# 8086_ELEVATOR_PROJECT.net
KiCad netlist of a schematic drawn in EasyEDA
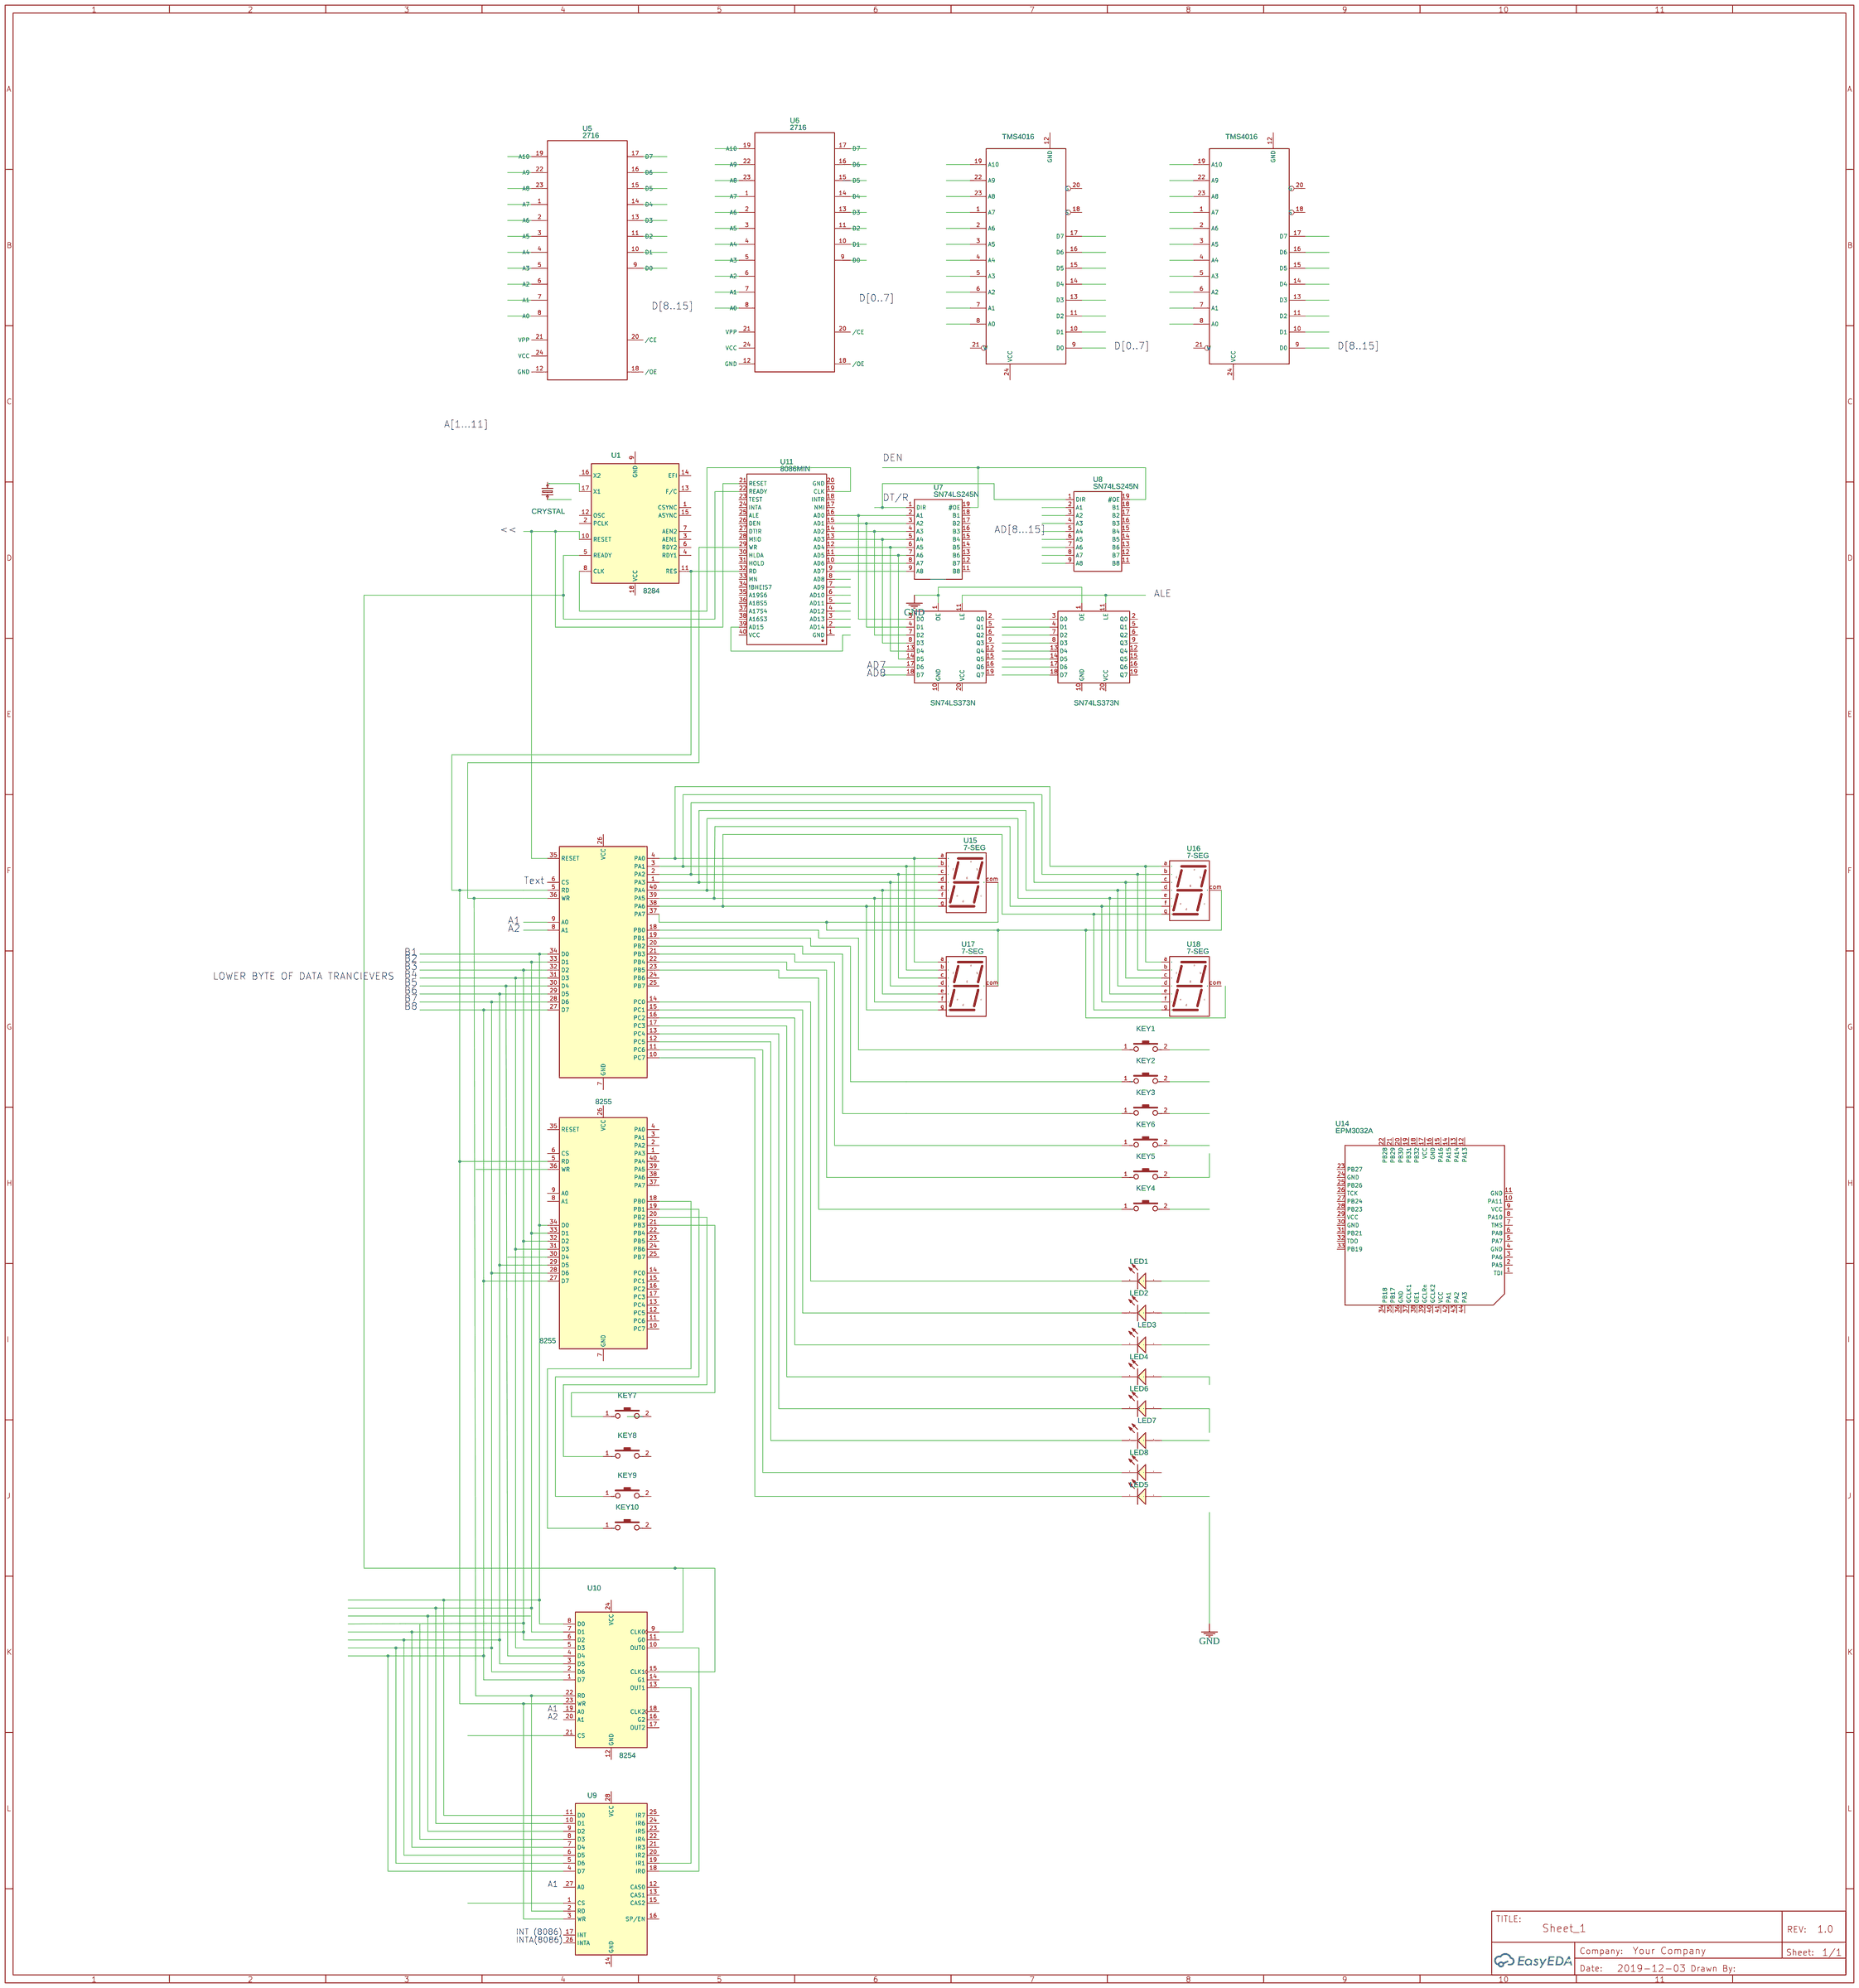
[diagram p0: schematic sheet]

(export (version "E")
  (design (tool "Eeschema 10.0.6"))
  (components
    (comp (ref "KEY1")
      (value "6*6*5 Silicone silent key button")
      (fields (field (name "BOM_Supplier Part") "C61120"))
      (libsource (lib "") (part "Unknown_1300_1140"))
    )
    (comp (ref "KEY2")
      (value "6*6*5 Silicone silent key button")
      (fields (field (name "BOM_Supplier Part") "C61120"))
      (libsource (lib "") (part "Unknown_1300_1180"))
    )
    (comp (ref "KEY3")
      (value "6*6*5 Silicone silent key button")
      (fields (field (name "BOM_Supplier Part") "C61120"))
      (libsource (lib "") (part "Unknown_1300_1220"))
    )
    (comp (ref "KEY4")
      (value "6*6*5 Silicone silent key button")
      (fields (field (name "BOM_Supplier Part") "C61120"))
      (libsource (lib "") (part "Unknown_1300_1340"))
    )
    (comp (ref "KEY5")
      (value "6*6*5 Silicone silent key button")
      (fields (field (name "BOM_Supplier Part") "C61120"))
      (libsource (lib "") (part "Unknown_1300_1300"))
    )
    (comp (ref "KEY6")
      (value "6*6*5 Silicone silent key button")
      (fields (field (name "BOM_Supplier Part") "C61120"))
      (libsource (lib "") (part "Unknown_1300_1260"))
    )
    (comp (ref "KEY7")
      (value "6*6*5 Silicone silent key button")
      (fields (field (name "BOM_Supplier Part") "C61120"))
      (libsource (lib "") (part "Unknown_650_1600"))
    )
    (comp (ref "KEY8")
      (value "6*6*5 Silicone silent key button")
      (fields (field (name "BOM_Supplier Part") "C61120"))
      (libsource (lib "") (part "Unknown_650_1650"))
    )
    (comp (ref "KEY9")
      (value "6*6*5 Silicone silent key button")
      (fields (field (name "BOM_Supplier Part") "C61120"))
      (libsource (lib "") (part "Unknown_650_1700"))
    )
    (comp (ref "KEY10")
      (value "6*6*5 Silicone silent key button")
      (fields (field (name "BOM_Supplier Part") "C61120"))
      (libsource (lib "") (part "Unknown_650_1740"))
    )
    (comp (ref "LED1")
      (value "LEDBlue light")
      (fields (field (name "BOM_Supplier Part") "C69273"))
      (libsource (lib "") (part "Unknown_1300_1430"))
    )
    (comp (ref "LED2")
      (value "LEDBlue light")
      (fields (field (name "BOM_Supplier Part") "C69273"))
      (libsource (lib "") (part "Unknown_1300_1470"))
    )
    (comp (ref "LED3")
      (value "LEDBlue light")
      (fields (field (name "BOM_Supplier Part") "C69273"))
      (libsource (lib "") (part "Unknown_1300_1510"))
    )
    (comp (ref "LED4")
      (value "LEDBlue light")
      (fields (field (name "BOM_Supplier Part") "C69273"))
      (libsource (lib "") (part "Unknown_1300_1550"))
    )
    (comp (ref "LED5")
      (value "LEDBlue light")
      (fields (field (name "BOM_Supplier Part") "C69273"))
      (libsource (lib "") (part "Unknown_1300_1700"))
    )
    (comp (ref "LED6")
      (value "LEDBlue light")
      (fields (field (name "BOM_Supplier Part") "C69273"))
      (libsource (lib "") (part "Unknown_1300_1590"))
    )
    (comp (ref "LED7")
      (value "LEDBlue light")
      (fields (field (name "BOM_Supplier Part") "C69273"))
      (libsource (lib "") (part "Unknown_1300_1630"))
    )
    (comp (ref "LED8")
      (value "LEDBlue light")
      (fields (field (name "BOM_Supplier Part") "C69273"))
      (libsource (lib "") (part "Unknown_1300_1670"))
    )
    (comp (ref "Q1") (value "CRYSTAL") (libsource (lib "") (part "Unknown_550_440")))
    (comp (ref "U1") (value "8284") (libsource (lib "") (part "Unknown_660_480")))
    (comp (ref "U2") (value "TMS4016") (libsource (lib "") (part "Unknown_1150_140")))
    (comp (ref "U3") (value "TMS4016") (libsource (lib "") (part "Unknown_1430_140")))
    (comp (ref "U4") (value "8255") (libsource (lib "") (part "Unknown_620_1030")))
    (comp (ref "U5")
      (value "2716")
      (fields (field (name "BOM_Manufacturer Part") "27C16"))
      (libsource (lib "") (part "Unknown_550_130"))
    )
    (comp (ref "U6")
      (value "2716")
      (fields (field (name "BOM_Manufacturer Part") "27C16"))
      (libsource (lib "") (part "Unknown_810_120"))
    )
    (comp (ref "U7")
      (value "SN74LS245N")
      (fields (field (name "BOM_Supplier Part") "C352966"))
      (libsource (lib "") (part "Unknown_1040_510"))
    )
    (comp (ref "U8")
      (value "SN74LS245N")
      (fields (field (name "BOM_Supplier Part") "C352966"))
      (libsource (lib "") (part "Unknown_1240_500"))
    )
    (comp (ref "U9") (value "8259") (libsource (lib "") (part "Unknown_630_2180")))
    (comp (ref "U10") (value "8254") (libsource (lib "") (part "Unknown_630_1930")))
    (comp (ref "U11") (value "8086MIN") (libsource (lib "") (part "Unknown_850_520")))
    (comp (ref "U12")
      (value "SN74LS373N")
      (fields (field (name "BOM_Supplier Part") "C10423"))
      (libsource (lib "") (part "Unknown_1190_600"))
    )
    (comp (ref "U13")
      (value "SN74LS373N")
      (fields (field (name "BOM_Supplier Part") "C10423"))
      (libsource (lib "") (part "Unknown_1010_600"))
    )
    (comp (ref "U14") (value "EPM3032A") (libsource (lib "") (part "Unknown_1650_1360")))
    (comp (ref "U15") (value "7-SEG") (libsource (lib "") (part "Unknown_1080_930")))
    (comp (ref "U16") (value "7-SEG") (libsource (lib "") (part "Unknown_1360_940")))
    (comp (ref "U17") (value "7-SEG") (libsource (lib "") (part "Unknown_1080_1060")))
    (comp (ref "U18") (value "7-SEG") (libsource (lib "") (part "Unknown_1360_1060")))
    (comp (ref "U19") (value "8255") (libsource (lib "") (part "Unknown_620_1370")))
  )
  (nets
    (net (code "1") (name "GND") (class "Default")
      (node (ref "U12") (pin "1") (pinfunction "OE_1") (pintype "unspecified"))
      (node (ref "U13") (pin "1") (pinfunction "OE_1") (pintype "unspecified"))
    )
    (net (code "2") (name "Net-(U1-CLK)") (class "Default")
      (node (ref "U1") (pin "8") (pinfunction "CLK_8") (pintype "output"))
      (node (ref "U11") (pin "19") (pinfunction "CLK_19") (pintype "unspecified"))
    )
    (net (code "3") (name "Net-(U1-READY)") (class "Default")
      (node (ref "U1") (pin "5") (pinfunction "READY_5") (pintype "output"))
      (node (ref "U10") (pin "15") (pinfunction "CLK1_15") (pintype "input"))
      (node (ref "U10") (pin "9") (pinfunction "CLK0_9") (pintype "input"))
      (node (ref "U11") (pin "22") (pinfunction "READY_22") (pintype "unspecified"))
    )
    (net (code "4") (name "Net-(U1-RES)") (class "Default")
      (node (ref "U1") (pin "11") (pinfunction "RES_11") (pintype "input"))
      (node (ref "U10") (pin "23") (pinfunction "WR_23") (pintype "input"))
      (node (ref "U11") (pin "32") (pinfunction "RD_32") (pintype "unspecified"))
      (node (ref "U19") (pin "5") (pinfunction "RD_5") (pintype "input"))
      (node (ref "U4") (pin "5") (pinfunction "RD_5") (pintype "input"))
      (node (ref "U9") (pin "3") (pinfunction "WR_3") (pintype "input"))
    )
    (net (code "5") (name "Net-(U1-RESET)") (class "Default")
      (node (ref "U1") (pin "10") (pinfunction "RESET_10") (pintype "output"))
      (node (ref "U11") (pin "21") (pinfunction "RESET_21") (pintype "unspecified"))
      (node (ref "U4") (pin "35") (pinfunction "RESET_35") (pintype "input"))
    )
    (net (code "6") (name "Net-(U1-X1)") (class "Default")
      (node (ref "Q1") (pin "1") (pinfunction "1_1") (pintype "unspecified"))
      (node (ref "U1") (pin "17") (pinfunction "X1_17") (pintype "input"))
    )
    (net (code "7") (name "Net-(U4-PA0)") (class "Default")
      (node (ref "U15") (pin "a") (pinfunction "a_a") (pintype "input"))
      (node (ref "U16") (pin "a") (pinfunction "a_a") (pintype "input"))
      (node (ref "U17") (pin "a") (pinfunction "a_a") (pintype "input"))
      (node (ref "U18") (pin "a") (pinfunction "a_a") (pintype "input"))
      (node (ref "U4") (pin "4") (pinfunction "PA0_4") (pintype "bidirectional"))
    )
    (net (code "8") (name "Net-(U4-PA1)") (class "Default")
      (node (ref "U15") (pin "b") (pinfunction "b_b") (pintype "input"))
      (node (ref "U16") (pin "b") (pinfunction "b_b") (pintype "input"))
      (node (ref "U17") (pin "b") (pinfunction "b_b") (pintype "input"))
      (node (ref "U18") (pin "b") (pinfunction "b_b") (pintype "input"))
      (node (ref "U4") (pin "3") (pinfunction "PA1_3") (pintype "bidirectional"))
    )
    (net (code "9") (name "Net-(U4-PA2)") (class "Default")
      (node (ref "U15") (pin "c") (pinfunction "c_c") (pintype "input"))
      (node (ref "U16") (pin "c") (pinfunction "c_c") (pintype "input"))
      (node (ref "U17") (pin "c") (pinfunction "c_c") (pintype "input"))
      (node (ref "U18") (pin "c") (pinfunction "c_c") (pintype "input"))
      (node (ref "U4") (pin "2") (pinfunction "PA2_2") (pintype "bidirectional"))
    )
    (net (code "10") (name "Net-(U4-PA3)") (class "Default")
      (node (ref "U15") (pin "d") (pinfunction "d_d") (pintype "input"))
      (node (ref "U16") (pin "d") (pinfunction "d_d") (pintype "input"))
      (node (ref "U17") (pin "d") (pinfunction "d_d") (pintype "input"))
      (node (ref "U18") (pin "d") (pinfunction "d_d") (pintype "input"))
      (node (ref "U4") (pin "1") (pinfunction "PA3_1") (pintype "bidirectional"))
    )
    (net (code "11") (name "Net-(U4-PA4)") (class "Default")
      (node (ref "U15") (pin "e") (pinfunction "e_e") (pintype "input"))
      (node (ref "U16") (pin "e") (pinfunction "e_e") (pintype "input"))
      (node (ref "U17") (pin "e") (pinfunction "e_e") (pintype "input"))
      (node (ref "U18") (pin "e") (pinfunction "e_e") (pintype "input"))
      (node (ref "U4") (pin "40") (pinfunction "PA4_40") (pintype "bidirectional"))
    )
    (net (code "12") (name "Net-(U4-PA5)") (class "Default")
      (node (ref "U15") (pin "f") (pinfunction "f_f") (pintype "input"))
      (node (ref "U16") (pin "f") (pinfunction "f_f") (pintype "input"))
      (node (ref "U17") (pin "f") (pinfunction "f_f") (pintype "input"))
      (node (ref "U18") (pin "f") (pinfunction "f_f") (pintype "input"))
      (node (ref "U4") (pin "39") (pinfunction "PA5_39") (pintype "bidirectional"))
    )
    (net (code "13") (name "Net-(U4-PA6)") (class "Default")
      (node (ref "U15") (pin "g") (pinfunction "g_g") (pintype "input"))
      (node (ref "U16") (pin "g") (pinfunction "g_g") (pintype "input"))
      (node (ref "U17") (pin "g") (pinfunction "g_g") (pintype "input"))
      (node (ref "U18") (pin "g") (pinfunction "g_g") (pintype "input"))
      (node (ref "U4") (pin "38") (pinfunction "PA6_38") (pintype "bidirectional"))
    )
    (net (code "14") (name "Net-(U4-PA7)") (class "Default")
      (node (ref "U15") (pin "com") (pinfunction "com_com") (pintype "passive"))
      (node (ref "U16") (pin "com") (pinfunction "com_com") (pintype "passive"))
      (node (ref "U17") (pin "com") (pinfunction "com_com") (pintype "passive"))
      (node (ref "U4") (pin "37") (pinfunction "PA7_37") (pintype "bidirectional"))
    )
    (net (code "15") (name "Net-(U4-PB0)") (class "Default")
      (node (ref "KEY1") (pin "1") (pinfunction "1_1") (pintype "input"))
      (node (ref "U4") (pin "18") (pinfunction "PB0_18") (pintype "bidirectional"))
    )
    (net (code "16") (name "Net-(U4-PB1)") (class "Default")
      (node (ref "KEY2") (pin "1") (pinfunction "1_1") (pintype "input"))
      (node (ref "U4") (pin "19") (pinfunction "PB1_19") (pintype "bidirectional"))
    )
    (net (code "17") (name "Net-(U4-PB2)") (class "Default")
      (node (ref "KEY3") (pin "1") (pinfunction "1_1") (pintype "input"))
      (node (ref "U4") (pin "20") (pinfunction "PB2_20") (pintype "bidirectional"))
    )
    (net (code "18") (name "Net-(U4-PB3)") (class "Default")
      (node (ref "KEY6") (pin "1") (pinfunction "1_1") (pintype "input"))
      (node (ref "U4") (pin "21") (pinfunction "PB3_21") (pintype "bidirectional"))
    )
    (net (code "19") (name "Net-(U4-PB4)") (class "Default")
      (node (ref "KEY5") (pin "1") (pinfunction "1_1") (pintype "input"))
      (node (ref "U4") (pin "22") (pinfunction "PB4_22") (pintype "bidirectional"))
    )
    (net (code "20") (name "Net-(U4-PB5)") (class "Default")
      (node (ref "KEY4") (pin "1") (pinfunction "1_1") (pintype "input"))
      (node (ref "U4") (pin "23") (pinfunction "PB5_23") (pintype "bidirectional"))
    )
    (net (code "21") (name "Net-(U4-PC0)") (class "Default")
      (node (ref "LED1") (pin "2") (pinfunction "2_2") (pintype "input"))
      (node (ref "U4") (pin "14") (pinfunction "PC0_14") (pintype "bidirectional"))
    )
    (net (code "22") (name "Net-(U4-PC1)") (class "Default")
      (node (ref "LED2") (pin "2") (pinfunction "2_2") (pintype "input"))
      (node (ref "U4") (pin "15") (pinfunction "PC1_15") (pintype "bidirectional"))
    )
    (net (code "23") (name "Net-(U4-PC2)") (class "Default")
      (node (ref "LED3") (pin "2") (pinfunction "2_2") (pintype "input"))
      (node (ref "U4") (pin "16") (pinfunction "PC2_16") (pintype "bidirectional"))
    )
    (net (code "24") (name "Net-(U4-PC3)") (class "Default")
      (node (ref "LED4") (pin "2") (pinfunction "2_2") (pintype "input"))
      (node (ref "U4") (pin "17") (pinfunction "PC3_17") (pintype "bidirectional"))
    )
    (net (code "25") (name "Net-(U4-PC4)") (class "Default")
      (node (ref "LED6") (pin "2") (pinfunction "2_2") (pintype "input"))
      (node (ref "U4") (pin "13") (pinfunction "PC4_13") (pintype "bidirectional"))
    )
    (net (code "26") (name "Net-(U4-PC5)") (class "Default")
      (node (ref "LED7") (pin "2") (pinfunction "2_2") (pintype "input"))
      (node (ref "U4") (pin "12") (pinfunction "PC5_12") (pintype "bidirectional"))
    )
    (net (code "27") (name "Net-(U4-PC6)") (class "Default")
      (node (ref "LED8") (pin "2") (pinfunction "2_2") (pintype "input"))
      (node (ref "U4") (pin "11") (pinfunction "PC6_11") (pintype "bidirectional"))
    )
    (net (code "28") (name "Net-(U4-PC7)") (class "Default")
      (node (ref "LED5") (pin "2") (pinfunction "2_2") (pintype "input"))
      (node (ref "U4") (pin "10") (pinfunction "PC7_10") (pintype "bidirectional"))
    )
    (net (code "29") (name "Net-(U7-#OE)") (class "Default")
      (node (ref "U7") (pin "19") (pinfunction "#OE_19") (pintype "input"))
      (node (ref "U8") (pin "19") (pinfunction "#OE_19") (pintype "input"))
    )
    (net (code "30") (name "Net-(U7-DIR)") (class "Default")
      (node (ref "U7") (pin "1") (pinfunction "DIR_1") (pintype "unspecified"))
      (node (ref "U8") (pin "1") (pinfunction "DIR_1") (pintype "unspecified"))
    )
    (net (code "31") (name "Net-(U10-D0)") (class "Default")
      (node (ref "U10") (pin "8") (pinfunction "D0_8") (pintype "bidirectional"))
      (node (ref "U19") (pin "34") (pinfunction "D0_34") (pintype "bidirectional"))
      (node (ref "U4") (pin "34") (pinfunction "D0_34") (pintype "bidirectional"))
      (node (ref "U9") (pin "11") (pinfunction "D0_11") (pintype "bidirectional"))
    )
    (net (code "32") (name "Net-(U10-D1)") (class "Default")
      (node (ref "U10") (pin "7") (pinfunction "D1_7") (pintype "bidirectional"))
      (node (ref "U19") (pin "33") (pinfunction "D1_33") (pintype "bidirectional"))
      (node (ref "U4") (pin "33") (pinfunction "D1_33") (pintype "bidirectional"))
      (node (ref "U9") (pin "10") (pinfunction "D1_10") (pintype "bidirectional"))
    )
    (net (code "33") (name "Net-(U10-D2)") (class "Default")
      (node (ref "U10") (pin "6") (pinfunction "D2_6") (pintype "bidirectional"))
      (node (ref "U19") (pin "32") (pinfunction "D2_32") (pintype "bidirectional"))
      (node (ref "U4") (pin "32") (pinfunction "D2_32") (pintype "bidirectional"))
      (node (ref "U9") (pin "7") (pinfunction "D4_7") (pintype "bidirectional"))
    )
    (net (code "34") (name "Net-(U10-D3)") (class "Default")
      (node (ref "U10") (pin "5") (pinfunction "D3_5") (pintype "bidirectional"))
      (node (ref "U19") (pin "31") (pinfunction "D3_31") (pintype "bidirectional"))
      (node (ref "U4") (pin "31") (pinfunction "D3_31") (pintype "bidirectional"))
    )
    (net (code "35") (name "Net-(U10-D4)") (class "Default")
      (node (ref "U10") (pin "4") (pinfunction "D4_4") (pintype "bidirectional"))
      (node (ref "U4") (pin "30") (pinfunction "D4_30") (pintype "bidirectional"))
    )
    (net (code "36") (name "Net-(U10-D5)") (class "Default")
      (node (ref "U10") (pin "3") (pinfunction "D5_3") (pintype "bidirectional"))
      (node (ref "U19") (pin "29") (pinfunction "D5_29") (pintype "bidirectional"))
      (node (ref "U4") (pin "29") (pinfunction "D5_29") (pintype "bidirectional"))
      (node (ref "U9") (pin "6") (pinfunction "D5_6") (pintype "bidirectional"))
    )
    (net (code "37") (name "Net-(U10-D6)") (class "Default")
      (node (ref "U10") (pin "2") (pinfunction "D6_2") (pintype "bidirectional"))
      (node (ref "U19") (pin "28") (pinfunction "D6_28") (pintype "bidirectional"))
      (node (ref "U4") (pin "28") (pinfunction "D6_28") (pintype "bidirectional"))
      (node (ref "U9") (pin "5") (pinfunction "D6_5") (pintype "bidirectional"))
    )
    (net (code "38") (name "Net-(U10-D7)") (class "Default")
      (node (ref "U10") (pin "1") (pinfunction "D7_1") (pintype "bidirectional"))
      (node (ref "U19") (pin "27") (pinfunction "D7_27") (pintype "bidirectional"))
      (node (ref "U4") (pin "27") (pinfunction "D7_27") (pintype "bidirectional"))
      (node (ref "U9") (pin "4") (pinfunction "D7_4") (pintype "bidirectional"))
    )
    (net (code "39") (name "Net-(U10-OUT0)") (class "Default")
      (node (ref "U10") (pin "10") (pinfunction "OUT0_10") (pintype "output"))
      (node (ref "U9") (pin "18") (pinfunction "IR0_18") (pintype "input"))
    )
    (net (code "40") (name "Net-(U10-OUT1)") (class "Default")
      (node (ref "U10") (pin "13") (pinfunction "OUT1_13") (pintype "output"))
      (node (ref "U9") (pin "19") (pinfunction "IR1_19") (pintype "input"))
    )
    (net (code "41") (name "Net-(U10-RD)") (class "Default")
      (node (ref "U10") (pin "22") (pinfunction "RD_22") (pintype "input"))
      (node (ref "U11") (pin "29") (pinfunction "WR_29") (pintype "unspecified"))
      (node (ref "U4") (pin "36") (pinfunction "WR_36") (pintype "input"))
      (node (ref "U9") (pin "2") (pinfunction "RD_2") (pintype "input"))
    )
    (net (code "42") (name "Net-(U11-AD0)") (class "Default")
      (node (ref "U11") (pin "16") (pinfunction "AD0_16") (pintype "unspecified"))
      (node (ref "U13") (pin "3") (pinfunction "D0_3") (pintype "unspecified"))
      (node (ref "U7") (pin "2") (pinfunction "A1_2") (pintype "unspecified"))
    )
    (net (code "43") (name "Net-(U11-AD1)") (class "Default")
      (node (ref "U11") (pin "15") (pinfunction "AD1_15") (pintype "unspecified"))
      (node (ref "U13") (pin "4") (pinfunction "D1_4") (pintype "unspecified"))
      (node (ref "U7") (pin "3") (pinfunction "A2_3") (pintype "unspecified"))
    )
    (net (code "44") (name "Net-(U11-AD2)") (class "Default")
      (node (ref "U11") (pin "14") (pinfunction "AD2_14") (pintype "unspecified"))
      (node (ref "U13") (pin "7") (pinfunction "D2_7") (pintype "unspecified"))
      (node (ref "U7") (pin "4") (pinfunction "A3_4") (pintype "unspecified"))
    )
    (net (code "45") (name "Net-(U11-AD3)") (class "Default")
      (node (ref "U11") (pin "13") (pinfunction "AD3_13") (pintype "unspecified"))
      (node (ref "U13") (pin "8") (pinfunction "D3_8") (pintype "unspecified"))
      (node (ref "U7") (pin "5") (pinfunction "A4_5") (pintype "unspecified"))
    )
    (net (code "46") (name "Net-(U11-AD4)") (class "Default")
      (node (ref "U11") (pin "12") (pinfunction "AD4_12") (pintype "unspecified"))
      (node (ref "U13") (pin "13") (pinfunction "D4_13") (pintype "unspecified"))
      (node (ref "U7") (pin "6") (pinfunction "A5_6") (pintype "unspecified"))
    )
    (net (code "47") (name "Net-(U11-AD5)") (class "Default")
      (node (ref "U11") (pin "11") (pinfunction "AD5_11") (pintype "unspecified"))
      (node (ref "U13") (pin "14") (pinfunction "D5_14") (pintype "unspecified"))
      (node (ref "U7") (pin "7") (pinfunction "A6_7") (pintype "unspecified"))
    )
    (net (code "48") (name "Net-(U11-AD6)") (class "Default")
      (node (ref "U11") (pin "10") (pinfunction "AD6_10") (pintype "unspecified"))
      (node (ref "U7") (pin "8") (pinfunction "A7_8") (pintype "unspecified"))
    )
    (net (code "49") (name "Net-(U11-AD7)") (class "Default")
      (node (ref "U11") (pin "9") (pinfunction "AD7_9") (pintype "unspecified"))
      (node (ref "U7") (pin "9") (pinfunction "A8_9") (pintype "bidirectional"))
    )
    (net (code "50") (name "Net-(U12-LE)") (class "Default")
      (node (ref "U12") (pin "11") (pinfunction "LE_11") (pintype "unspecified"))
      (node (ref "U13") (pin "11") (pinfunction "LE_11") (pintype "unspecified"))
    )
    (net (code "51") (name "Net-(U19-PB0)") (class "Default")
      (node (ref "KEY10") (pin "1") (pinfunction "1_1") (pintype "input"))
      (node (ref "U19") (pin "18") (pinfunction "PB0_18") (pintype "bidirectional"))
    )
    (net (code "52") (name "Net-(U19-PB1)") (class "Default")
      (node (ref "KEY9") (pin "1") (pinfunction "1_1") (pintype "input"))
      (node (ref "U19") (pin "19") (pinfunction "PB1_19") (pintype "bidirectional"))
    )
    (net (code "53") (name "Net-(U19-PB2)") (class "Default")
      (node (ref "KEY8") (pin "1") (pinfunction "1_1") (pintype "input"))
      (node (ref "U19") (pin "20") (pinfunction "PB2_20") (pintype "bidirectional"))
    )
    (net (code "54") (name "Net-(U19-PB3)") (class "Default")
      (node (ref "KEY7") (pin "1") (pinfunction "1_1") (pintype "input"))
      (node (ref "U19") (pin "21") (pinfunction "PB3_21") (pintype "bidirectional"))
    )
    (net (code "55") (name "unconnected-(KEY1-Pad2)") (class "Default")
      (node (ref "KEY1") (pin "2") (pinfunction "2_2") (pintype "input"))
    )
    (net (code "56") (name "unconnected-(KEY2-Pad2)") (class "Default")
      (node (ref "KEY2") (pin "2") (pinfunction "2_2") (pintype "input"))
    )
    (net (code "57") (name "unconnected-(KEY3-Pad2)") (class "Default")
      (node (ref "KEY3") (pin "2") (pinfunction "2_2") (pintype "input"))
    )
    (net (code "58") (name "unconnected-(KEY4-Pad2)") (class "Default")
      (node (ref "KEY4") (pin "2") (pinfunction "2_2") (pintype "input"))
    )
    (net (code "59") (name "unconnected-(KEY5-Pad2)") (class "Default")
      (node (ref "KEY5") (pin "2") (pinfunction "2_2") (pintype "input"))
    )
    (net (code "60") (name "unconnected-(KEY6-Pad2)") (class "Default")
      (node (ref "KEY6") (pin "2") (pinfunction "2_2") (pintype "input"))
    )
    (net (code "61") (name "unconnected-(KEY7-Pad2)") (class "Default")
      (node (ref "KEY7") (pin "2") (pinfunction "2_2") (pintype "input"))
    )
    (net (code "62") (name "unconnected-(KEY8-Pad2)") (class "Default")
      (node (ref "KEY8") (pin "2") (pinfunction "2_2") (pintype "input"))
    )
    (net (code "63") (name "unconnected-(KEY9-Pad2)") (class "Default")
      (node (ref "KEY9") (pin "2") (pinfunction "2_2") (pintype "input"))
    )
    (net (code "64") (name "unconnected-(KEY10-Pad2)") (class "Default")
      (node (ref "KEY10") (pin "2") (pinfunction "2_2") (pintype "input"))
    )
    (net (code "65") (name "unconnected-(LED1-Pad1)") (class "Default")
      (node (ref "LED1") (pin "1") (pinfunction "1_1") (pintype "input"))
    )
    (net (code "66") (name "unconnected-(LED2-Pad1)") (class "Default")
      (node (ref "LED2") (pin "1") (pinfunction "1_1") (pintype "input"))
    )
    (net (code "67") (name "unconnected-(LED3-Pad1)") (class "Default")
      (node (ref "LED3") (pin "1") (pinfunction "1_1") (pintype "input"))
    )
    (net (code "68") (name "unconnected-(LED4-Pad1)") (class "Default")
      (node (ref "LED4") (pin "1") (pinfunction "1_1") (pintype "input"))
    )
    (net (code "69") (name "unconnected-(LED5-Pad1)") (class "Default")
      (node (ref "LED5") (pin "1") (pinfunction "1_1") (pintype "input"))
    )
    (net (code "70") (name "unconnected-(LED6-Pad1)") (class "Default")
      (node (ref "LED6") (pin "1") (pinfunction "1_1") (pintype "input"))
    )
    (net (code "71") (name "unconnected-(LED7-Pad1)") (class "Default")
      (node (ref "LED7") (pin "1") (pinfunction "1_1") (pintype "input"))
    )
    (net (code "72") (name "unconnected-(LED8-Pad1)") (class "Default")
      (node (ref "LED8") (pin "1") (pinfunction "1_1") (pintype "input"))
    )
    (net (code "73") (name "unconnected-(Q1-Pad2)") (class "Default")
      (node (ref "Q1") (pin "2") (pinfunction "2_2") (pintype "unspecified"))
    )
    (net (code "74") (name "unconnected-(U1-AEN1-Pad3)") (class "Default")
      (node (ref "U1") (pin "3") (pinfunction "AEN1_3") (pintype "input"))
    )
    (net (code "75") (name "unconnected-(U1-AEN2-Pad7)") (class "Default")
      (node (ref "U1") (pin "7") (pinfunction "AEN2_7") (pintype "input"))
    )
    (net (code "76") (name "unconnected-(U1-ASYNC-Pad15)") (class "Default")
      (node (ref "U1") (pin "15") (pinfunction "ASYNC_15") (pintype "input"))
    )
    (net (code "77") (name "unconnected-(U1-CSYNC-Pad1)") (class "Default")
      (node (ref "U1") (pin "1") (pinfunction "CSYNC_1") (pintype "input"))
    )
    (net (code "78") (name "unconnected-(U1-EFI-Pad14)") (class "Default")
      (node (ref "U1") (pin "14") (pinfunction "EFI_14") (pintype "input"))
    )
    (net (code "79") (name "unconnected-(U1-F{slash}C-Pad13)") (class "Default")
      (node (ref "U1") (pin "13") (pinfunction "F/C_13") (pintype "input"))
    )
    (net (code "80") (name "unconnected-(U1-GND-Pad9)") (class "Default")
      (node (ref "U1") (pin "9") (pinfunction "GND_9") (pintype "bidirectional"))
    )
    (net (code "81") (name "unconnected-(U1-OSC-Pad12)") (class "Default")
      (node (ref "U1") (pin "12") (pinfunction "OSC_12") (pintype "output"))
    )
    (net (code "82") (name "unconnected-(U1-PCLK-Pad2)") (class "Default")
      (node (ref "U1") (pin "2") (pinfunction "PCLK_2") (pintype "output"))
    )
    (net (code "83") (name "unconnected-(U1-RDY1-Pad4)") (class "Default")
      (node (ref "U1") (pin "4") (pinfunction "RDY1_4") (pintype "input"))
    )
    (net (code "84") (name "unconnected-(U1-RDY2-Pad6)") (class "Default")
      (node (ref "U1") (pin "6") (pinfunction "RDY2_6") (pintype "input"))
    )
    (net (code "85") (name "unconnected-(U1-VCC-Pad18)") (class "Default")
      (node (ref "U1") (pin "18") (pinfunction "VCC_18") (pintype "bidirectional"))
    )
    (net (code "86") (name "unconnected-(U1-X2-Pad16)") (class "Default")
      (node (ref "U1") (pin "16") (pinfunction "X2_16") (pintype "output"))
    )
    (net (code "87") (name "unconnected-(U2-A0-Pad8)") (class "Default")
      (node (ref "U2") (pin "8") (pinfunction "A0_8") (pintype "unspecified"))
    )
    (net (code "88") (name "unconnected-(U2-A1-Pad7)") (class "Default")
      (node (ref "U2") (pin "7") (pinfunction "A1_7") (pintype "unspecified"))
    )
    (net (code "89") (name "unconnected-(U2-A2-Pad6)") (class "Default")
      (node (ref "U2") (pin "6") (pinfunction "A2_6") (pintype "unspecified"))
    )
    (net (code "90") (name "unconnected-(U2-A3-Pad5)") (class "Default")
      (node (ref "U2") (pin "5") (pinfunction "A3_5") (pintype "unspecified"))
    )
    (net (code "91") (name "unconnected-(U2-A4-Pad4)") (class "Default")
      (node (ref "U2") (pin "4") (pinfunction "A4_4") (pintype "unspecified"))
    )
    (net (code "92") (name "unconnected-(U2-A5-Pad3)") (class "Default")
      (node (ref "U2") (pin "3") (pinfunction "A5_3") (pintype "unspecified"))
    )
    (net (code "93") (name "unconnected-(U2-A6-Pad2)") (class "Default")
      (node (ref "U2") (pin "2") (pinfunction "A6_2") (pintype "unspecified"))
    )
    (net (code "94") (name "unconnected-(U2-A7-Pad1)") (class "Default")
      (node (ref "U2") (pin "1") (pinfunction "A7_1") (pintype "unspecified"))
    )
    (net (code "95") (name "unconnected-(U2-A8-Pad23)") (class "Default")
      (node (ref "U2") (pin "23") (pinfunction "A8_23") (pintype "unspecified"))
    )
    (net (code "96") (name "unconnected-(U2-A9-Pad22)") (class "Default")
      (node (ref "U2") (pin "22") (pinfunction "A9_22") (pintype "unspecified"))
    )
    (net (code "97") (name "unconnected-(U2-A10-Pad19)") (class "Default")
      (node (ref "U2") (pin "19") (pinfunction "A10_19") (pintype "unspecified"))
    )
    (net (code "98") (name "unconnected-(U2-D0-Pad9)") (class "Default")
      (node (ref "U2") (pin "9") (pinfunction "D0_9") (pintype "unspecified"))
    )
    (net (code "99") (name "unconnected-(U2-D1-Pad10)") (class "Default")
      (node (ref "U2") (pin "10") (pinfunction "D1_10") (pintype "unspecified"))
    )
    (net (code "100") (name "unconnected-(U2-D2-Pad11)") (class "Default")
      (node (ref "U2") (pin "11") (pinfunction "D2_11") (pintype "unspecified"))
    )
    (net (code "101") (name "unconnected-(U2-D3-Pad13)") (class "Default")
      (node (ref "U2") (pin "13") (pinfunction "D3_13") (pintype "unspecified"))
    )
    (net (code "102") (name "unconnected-(U2-D4-Pad14)") (class "Default")
      (node (ref "U2") (pin "14") (pinfunction "D4_14") (pintype "unspecified"))
    )
    (net (code "103") (name "unconnected-(U2-D5-Pad15)") (class "Default")
      (node (ref "U2") (pin "15") (pinfunction "D5_15") (pintype "unspecified"))
    )
    (net (code "104") (name "unconnected-(U2-D6-Pad16)") (class "Default")
      (node (ref "U2") (pin "16") (pinfunction "D6_16") (pintype "unspecified"))
    )
    (net (code "105") (name "unconnected-(U2-D7-Pad17)") (class "Default")
      (node (ref "U2") (pin "17") (pinfunction "D7_17") (pintype "unspecified"))
    )
    (net (code "106") (name "unconnected-(U2-G-Pad20)") (class "Default")
      (node (ref "U2") (pin "20") (pinfunction "G_20") (pintype "unspecified"))
    )
    (net (code "107") (name "unconnected-(U2-GND-Pad12)") (class "Default")
      (node (ref "U2") (pin "12") (pinfunction "GND_12") (pintype "unspecified"))
    )
    (net (code "108") (name "unconnected-(U2-S-Pad18)") (class "Default")
      (node (ref "U2") (pin "18") (pinfunction "S_18") (pintype "unspecified"))
    )
    (net (code "109") (name "unconnected-(U2-VCC-Pad24)") (class "Default")
      (node (ref "U2") (pin "24") (pinfunction "VCC_24") (pintype "unspecified"))
    )
    (net (code "110") (name "unconnected-(U2-W-Pad21)") (class "Default")
      (node (ref "U2") (pin "21") (pinfunction "W_21") (pintype "unspecified"))
    )
    (net (code "111") (name "unconnected-(U3-A0-Pad8)") (class "Default")
      (node (ref "U3") (pin "8") (pinfunction "A0_8") (pintype "unspecified"))
    )
    (net (code "112") (name "unconnected-(U3-A1-Pad7)") (class "Default")
      (node (ref "U3") (pin "7") (pinfunction "A1_7") (pintype "unspecified"))
    )
    (net (code "113") (name "unconnected-(U3-A2-Pad6)") (class "Default")
      (node (ref "U3") (pin "6") (pinfunction "A2_6") (pintype "unspecified"))
    )
    (net (code "114") (name "unconnected-(U3-A3-Pad5)") (class "Default")
      (node (ref "U3") (pin "5") (pinfunction "A3_5") (pintype "unspecified"))
    )
    (net (code "115") (name "unconnected-(U3-A4-Pad4)") (class "Default")
      (node (ref "U3") (pin "4") (pinfunction "A4_4") (pintype "unspecified"))
    )
    (net (code "116") (name "unconnected-(U3-A5-Pad3)") (class "Default")
      (node (ref "U3") (pin "3") (pinfunction "A5_3") (pintype "unspecified"))
    )
    (net (code "117") (name "unconnected-(U3-A6-Pad2)") (class "Default")
      (node (ref "U3") (pin "2") (pinfunction "A6_2") (pintype "unspecified"))
    )
    (net (code "118") (name "unconnected-(U3-A7-Pad1)") (class "Default")
      (node (ref "U3") (pin "1") (pinfunction "A7_1") (pintype "unspecified"))
    )
    (net (code "119") (name "unconnected-(U3-A8-Pad23)") (class "Default")
      (node (ref "U3") (pin "23") (pinfunction "A8_23") (pintype "unspecified"))
    )
    (net (code "120") (name "unconnected-(U3-A9-Pad22)") (class "Default")
      (node (ref "U3") (pin "22") (pinfunction "A9_22") (pintype "unspecified"))
    )
    (net (code "121") (name "unconnected-(U3-A10-Pad19)") (class "Default")
      (node (ref "U3") (pin "19") (pinfunction "A10_19") (pintype "unspecified"))
    )
    (net (code "122") (name "unconnected-(U3-D0-Pad9)") (class "Default")
      (node (ref "U3") (pin "9") (pinfunction "D0_9") (pintype "unspecified"))
    )
    (net (code "123") (name "unconnected-(U3-D1-Pad10)") (class "Default")
      (node (ref "U3") (pin "10") (pinfunction "D1_10") (pintype "unspecified"))
    )
    (net (code "124") (name "unconnected-(U3-D2-Pad11)") (class "Default")
      (node (ref "U3") (pin "11") (pinfunction "D2_11") (pintype "unspecified"))
    )
    (net (code "125") (name "unconnected-(U3-D3-Pad13)") (class "Default")
      (node (ref "U3") (pin "13") (pinfunction "D3_13") (pintype "unspecified"))
    )
    (net (code "126") (name "unconnected-(U3-D4-Pad14)") (class "Default")
      (node (ref "U3") (pin "14") (pinfunction "D4_14") (pintype "unspecified"))
    )
    (net (code "127") (name "unconnected-(U3-D5-Pad15)") (class "Default")
      (node (ref "U3") (pin "15") (pinfunction "D5_15") (pintype "unspecified"))
    )
    (net (code "128") (name "unconnected-(U3-D6-Pad16)") (class "Default")
      (node (ref "U3") (pin "16") (pinfunction "D6_16") (pintype "unspecified"))
    )
    (net (code "129") (name "unconnected-(U3-D7-Pad17)") (class "Default")
      (node (ref "U3") (pin "17") (pinfunction "D7_17") (pintype "unspecified"))
    )
    (net (code "130") (name "unconnected-(U3-G-Pad20)") (class "Default")
      (node (ref "U3") (pin "20") (pinfunction "G_20") (pintype "unspecified"))
    )
    (net (code "131") (name "unconnected-(U3-GND-Pad12)") (class "Default")
      (node (ref "U3") (pin "12") (pinfunction "GND_12") (pintype "unspecified"))
    )
    (net (code "132") (name "unconnected-(U3-S-Pad18)") (class "Default")
      (node (ref "U3") (pin "18") (pinfunction "S_18") (pintype "unspecified"))
    )
    (net (code "133") (name "unconnected-(U3-VCC-Pad24)") (class "Default")
      (node (ref "U3") (pin "24") (pinfunction "VCC_24") (pintype "unspecified"))
    )
    (net (code "134") (name "unconnected-(U3-W-Pad21)") (class "Default")
      (node (ref "U3") (pin "21") (pinfunction "W_21") (pintype "unspecified"))
    )
    (net (code "135") (name "unconnected-(U4-A0-Pad9)") (class "Default")
      (node (ref "U4") (pin "9") (pinfunction "A0_9") (pintype "input"))
    )
    (net (code "136") (name "unconnected-(U4-A1-Pad8)") (class "Default")
      (node (ref "U4") (pin "8") (pinfunction "A1_8") (pintype "input"))
    )
    (net (code "137") (name "unconnected-(U4-CS-Pad6)") (class "Default")
      (node (ref "U4") (pin "6") (pinfunction "CS_6") (pintype "input"))
    )
    (net (code "138") (name "unconnected-(U4-GND-Pad7)") (class "Default")
      (node (ref "U4") (pin "7") (pinfunction "GND_7") (pintype "bidirectional"))
    )
    (net (code "139") (name "unconnected-(U4-PB6-Pad24)") (class "Default")
      (node (ref "U4") (pin "24") (pinfunction "PB6_24") (pintype "bidirectional"))
    )
    (net (code "140") (name "unconnected-(U4-PB7-Pad25)") (class "Default")
      (node (ref "U4") (pin "25") (pinfunction "PB7_25") (pintype "bidirectional"))
    )
    (net (code "141") (name "unconnected-(U4-VCC-Pad26)") (class "Default")
      (node (ref "U4") (pin "26") (pinfunction "VCC_26") (pintype "bidirectional"))
    )
    (net (code "142") (name "unconnected-(U5-A0-Pad8)") (class "Default")
      (node (ref "U5") (pin "8") (pinfunction "A0_8") (pintype "unspecified"))
    )
    (net (code "143") (name "unconnected-(U5-A1-Pad7)") (class "Default")
      (node (ref "U5") (pin "7") (pinfunction "A1_7") (pintype "unspecified"))
    )
    (net (code "144") (name "unconnected-(U5-A2-Pad6)") (class "Default")
      (node (ref "U5") (pin "6") (pinfunction "A2_6") (pintype "unspecified"))
    )
    (net (code "145") (name "unconnected-(U5-A3-Pad5)") (class "Default")
      (node (ref "U5") (pin "5") (pinfunction "A3_5") (pintype "unspecified"))
    )
    (net (code "146") (name "unconnected-(U5-A4-Pad4)") (class "Default")
      (node (ref "U5") (pin "4") (pinfunction "A4_4") (pintype "unspecified"))
    )
    (net (code "147") (name "unconnected-(U5-A5-Pad3)") (class "Default")
      (node (ref "U5") (pin "3") (pinfunction "A5_3") (pintype "unspecified"))
    )
    (net (code "148") (name "unconnected-(U5-A6-Pad2)") (class "Default")
      (node (ref "U5") (pin "2") (pinfunction "A6_2") (pintype "unspecified"))
    )
    (net (code "149") (name "unconnected-(U5-A7-Pad1)") (class "Default")
      (node (ref "U5") (pin "1") (pinfunction "A7_1") (pintype "unspecified"))
    )
    (net (code "150") (name "unconnected-(U5-A8-Pad23)") (class "Default")
      (node (ref "U5") (pin "23") (pinfunction "A8_23") (pintype "unspecified"))
    )
    (net (code "151") (name "unconnected-(U5-A9-Pad22)") (class "Default")
      (node (ref "U5") (pin "22") (pinfunction "A9_22") (pintype "unspecified"))
    )
    (net (code "152") (name "unconnected-(U5-A10-Pad19)") (class "Default")
      (node (ref "U5") (pin "19") (pinfunction "A10_19") (pintype "unspecified"))
    )
    (net (code "153") (name "unconnected-(U5-D0-Pad9)") (class "Default")
      (node (ref "U5") (pin "9") (pinfunction "D0_9") (pintype "unspecified"))
    )
    (net (code "154") (name "unconnected-(U5-D1-Pad10)") (class "Default")
      (node (ref "U5") (pin "10") (pinfunction "D1_10") (pintype "unspecified"))
    )
    (net (code "155") (name "unconnected-(U5-D2-Pad11)") (class "Default")
      (node (ref "U5") (pin "11") (pinfunction "D2_11") (pintype "unspecified"))
    )
    (net (code "156") (name "unconnected-(U5-D3-Pad13)") (class "Default")
      (node (ref "U5") (pin "13") (pinfunction "D3_13") (pintype "unspecified"))
    )
    (net (code "157") (name "unconnected-(U5-D4-Pad14)") (class "Default")
      (node (ref "U5") (pin "14") (pinfunction "D4_14") (pintype "unspecified"))
    )
    (net (code "158") (name "unconnected-(U5-D5-Pad15)") (class "Default")
      (node (ref "U5") (pin "15") (pinfunction "D5_15") (pintype "unspecified"))
    )
    (net (code "159") (name "unconnected-(U5-D6-Pad16)") (class "Default")
      (node (ref "U5") (pin "16") (pinfunction "D6_16") (pintype "unspecified"))
    )
    (net (code "160") (name "unconnected-(U5-D7-Pad17)") (class "Default")
      (node (ref "U5") (pin "17") (pinfunction "D7_17") (pintype "unspecified"))
    )
    (net (code "161") (name "unconnected-(U5-GND-Pad12)") (class "Default")
      (node (ref "U5") (pin "12") (pinfunction "GND_12") (pintype "unspecified"))
    )
    (net (code "162") (name "unconnected-(U5-VCC-Pad24)") (class "Default")
      (node (ref "U5") (pin "24") (pinfunction "VCC_24") (pintype "unspecified"))
    )
    (net (code "163") (name "unconnected-(U5-VPP-Pad21)") (class "Default")
      (node (ref "U5") (pin "21") (pinfunction "VPP_21") (pintype "unspecified"))
    )
    (net (code "164") (name "unconnected-(U5-{slash}CE-Pad20)") (class "Default")
      (node (ref "U5") (pin "20") (pinfunction "/CE_20") (pintype "unspecified"))
    )
    (net (code "165") (name "unconnected-(U5-{slash}OE-Pad18)") (class "Default")
      (node (ref "U5") (pin "18") (pinfunction "/OE_18") (pintype "unspecified"))
    )
    (net (code "166") (name "unconnected-(U6-A0-Pad8)") (class "Default")
      (node (ref "U6") (pin "8") (pinfunction "A0_8") (pintype "unspecified"))
    )
    (net (code "167") (name "unconnected-(U6-A1-Pad7)") (class "Default")
      (node (ref "U6") (pin "7") (pinfunction "A1_7") (pintype "unspecified"))
    )
    (net (code "168") (name "unconnected-(U6-A2-Pad6)") (class "Default")
      (node (ref "U6") (pin "6") (pinfunction "A2_6") (pintype "unspecified"))
    )
    (net (code "169") (name "unconnected-(U6-A3-Pad5)") (class "Default")
      (node (ref "U6") (pin "5") (pinfunction "A3_5") (pintype "unspecified"))
    )
    (net (code "170") (name "unconnected-(U6-A4-Pad4)") (class "Default")
      (node (ref "U6") (pin "4") (pinfunction "A4_4") (pintype "unspecified"))
    )
    (net (code "171") (name "unconnected-(U6-A5-Pad3)") (class "Default")
      (node (ref "U6") (pin "3") (pinfunction "A5_3") (pintype "unspecified"))
    )
    (net (code "172") (name "unconnected-(U6-A6-Pad2)") (class "Default")
      (node (ref "U6") (pin "2") (pinfunction "A6_2") (pintype "unspecified"))
    )
    (net (code "173") (name "unconnected-(U6-A7-Pad1)") (class "Default")
      (node (ref "U6") (pin "1") (pinfunction "A7_1") (pintype "unspecified"))
    )
    (net (code "174") (name "unconnected-(U6-A8-Pad23)") (class "Default")
      (node (ref "U6") (pin "23") (pinfunction "A8_23") (pintype "unspecified"))
    )
    (net (code "175") (name "unconnected-(U6-A9-Pad22)") (class "Default")
      (node (ref "U6") (pin "22") (pinfunction "A9_22") (pintype "unspecified"))
    )
    (net (code "176") (name "unconnected-(U6-A10-Pad19)") (class "Default")
      (node (ref "U6") (pin "19") (pinfunction "A10_19") (pintype "unspecified"))
    )
    (net (code "177") (name "unconnected-(U6-D0-Pad9)") (class "Default")
      (node (ref "U6") (pin "9") (pinfunction "D0_9") (pintype "unspecified"))
    )
    (net (code "178") (name "unconnected-(U6-D1-Pad10)") (class "Default")
      (node (ref "U6") (pin "10") (pinfunction "D1_10") (pintype "unspecified"))
    )
    (net (code "179") (name "unconnected-(U6-D2-Pad11)") (class "Default")
      (node (ref "U6") (pin "11") (pinfunction "D2_11") (pintype "unspecified"))
    )
    (net (code "180") (name "unconnected-(U6-D3-Pad13)") (class "Default")
      (node (ref "U6") (pin "13") (pinfunction "D3_13") (pintype "unspecified"))
    )
    (net (code "181") (name "unconnected-(U6-D4-Pad14)") (class "Default")
      (node (ref "U6") (pin "14") (pinfunction "D4_14") (pintype "unspecified"))
    )
    (net (code "182") (name "unconnected-(U6-D5-Pad15)") (class "Default")
      (node (ref "U6") (pin "15") (pinfunction "D5_15") (pintype "unspecified"))
    )
    (net (code "183") (name "unconnected-(U6-D6-Pad16)") (class "Default")
      (node (ref "U6") (pin "16") (pinfunction "D6_16") (pintype "unspecified"))
    )
    (net (code "184") (name "unconnected-(U6-D7-Pad17)") (class "Default")
      (node (ref "U6") (pin "17") (pinfunction "D7_17") (pintype "unspecified"))
    )
    (net (code "185") (name "unconnected-(U6-GND-Pad12)") (class "Default")
      (node (ref "U6") (pin "12") (pinfunction "GND_12") (pintype "unspecified"))
    )
    (net (code "186") (name "unconnected-(U6-VCC-Pad24)") (class "Default")
      (node (ref "U6") (pin "24") (pinfunction "VCC_24") (pintype "unspecified"))
    )
    (net (code "187") (name "unconnected-(U6-VPP-Pad21)") (class "Default")
      (node (ref "U6") (pin "21") (pinfunction "VPP_21") (pintype "unspecified"))
    )
    (net (code "188") (name "unconnected-(U6-{slash}CE-Pad20)") (class "Default")
      (node (ref "U6") (pin "20") (pinfunction "/CE_20") (pintype "unspecified"))
    )
    (net (code "189") (name "unconnected-(U6-{slash}OE-Pad18)") (class "Default")
      (node (ref "U6") (pin "18") (pinfunction "/OE_18") (pintype "unspecified"))
    )
    (net (code "190") (name "unconnected-(U7-B1-Pad18)") (class "Default")
      (node (ref "U7") (pin "18") (pinfunction "B1_18") (pintype "bidirectional"))
    )
    (net (code "191") (name "unconnected-(U7-B2-Pad17)") (class "Default")
      (node (ref "U7") (pin "17") (pinfunction "B2_17") (pintype "bidirectional"))
    )
    (net (code "192") (name "unconnected-(U7-B3-Pad16)") (class "Default")
      (node (ref "U7") (pin "16") (pinfunction "B3_16") (pintype "bidirectional"))
    )
    (net (code "193") (name "unconnected-(U7-B4-Pad15)") (class "Default")
      (node (ref "U7") (pin "15") (pinfunction "B4_15") (pintype "bidirectional"))
    )
    (net (code "194") (name "unconnected-(U7-B5-Pad14)") (class "Default")
      (node (ref "U7") (pin "14") (pinfunction "B5_14") (pintype "bidirectional"))
    )
    (net (code "195") (name "unconnected-(U7-B6-Pad13)") (class "Default")
      (node (ref "U7") (pin "13") (pinfunction "B6_13") (pintype "bidirectional"))
    )
    (net (code "196") (name "unconnected-(U7-B7-Pad12)") (class "Default")
      (node (ref "U7") (pin "12") (pinfunction "B7_12") (pintype "bidirectional"))
    )
    (net (code "197") (name "unconnected-(U7-B8-Pad11)") (class "Default")
      (node (ref "U7") (pin "11") (pinfunction "B8_11") (pintype "bidirectional"))
    )
    (net (code "198") (name "unconnected-(U8-A1-Pad2)") (class "Default")
      (node (ref "U8") (pin "2") (pinfunction "A1_2") (pintype "unspecified"))
    )
    (net (code "199") (name "unconnected-(U8-A2-Pad3)") (class "Default")
      (node (ref "U8") (pin "3") (pinfunction "A2_3") (pintype "unspecified"))
    )
    (net (code "200") (name "unconnected-(U8-A3-Pad4)") (class "Default")
      (node (ref "U8") (pin "4") (pinfunction "A3_4") (pintype "unspecified"))
    )
    (net (code "201") (name "unconnected-(U8-A4-Pad5)") (class "Default")
      (node (ref "U8") (pin "5") (pinfunction "A4_5") (pintype "unspecified"))
    )
    (net (code "202") (name "unconnected-(U8-A5-Pad6)") (class "Default")
      (node (ref "U8") (pin "6") (pinfunction "A5_6") (pintype "unspecified"))
    )
    (net (code "203") (name "unconnected-(U8-A6-Pad7)") (class "Default")
      (node (ref "U8") (pin "7") (pinfunction "A6_7") (pintype "unspecified"))
    )
    (net (code "204") (name "unconnected-(U8-A7-Pad8)") (class "Default")
      (node (ref "U8") (pin "8") (pinfunction "A7_8") (pintype "unspecified"))
    )
    (net (code "205") (name "unconnected-(U8-A8-Pad9)") (class "Default")
      (node (ref "U8") (pin "9") (pinfunction "A8_9") (pintype "bidirectional"))
    )
    (net (code "206") (name "unconnected-(U8-B1-Pad18)") (class "Default")
      (node (ref "U8") (pin "18") (pinfunction "B1_18") (pintype "bidirectional"))
    )
    (net (code "207") (name "unconnected-(U8-B2-Pad17)") (class "Default")
      (node (ref "U8") (pin "17") (pinfunction "B2_17") (pintype "bidirectional"))
    )
    (net (code "208") (name "unconnected-(U8-B3-Pad16)") (class "Default")
      (node (ref "U8") (pin "16") (pinfunction "B3_16") (pintype "bidirectional"))
    )
    (net (code "209") (name "unconnected-(U8-B4-Pad15)") (class "Default")
      (node (ref "U8") (pin "15") (pinfunction "B4_15") (pintype "bidirectional"))
    )
    (net (code "210") (name "unconnected-(U8-B5-Pad14)") (class "Default")
      (node (ref "U8") (pin "14") (pinfunction "B5_14") (pintype "bidirectional"))
    )
    (net (code "211") (name "unconnected-(U8-B6-Pad13)") (class "Default")
      (node (ref "U8") (pin "13") (pinfunction "B6_13") (pintype "bidirectional"))
    )
    (net (code "212") (name "unconnected-(U8-B7-Pad12)") (class "Default")
      (node (ref "U8") (pin "12") (pinfunction "B7_12") (pintype "bidirectional"))
    )
    (net (code "213") (name "unconnected-(U8-B8-Pad11)") (class "Default")
      (node (ref "U8") (pin "11") (pinfunction "B8_11") (pintype "bidirectional"))
    )
    (net (code "214") (name "unconnected-(U9-A0-Pad27)") (class "Default")
      (node (ref "U9") (pin "27") (pinfunction "A0_27") (pintype "input"))
    )
    (net (code "215") (name "unconnected-(U9-CAS0-Pad12)") (class "Default")
      (node (ref "U9") (pin "12") (pinfunction "CAS0_12") (pintype "input"))
    )
    (net (code "216") (name "unconnected-(U9-CAS1-Pad13)") (class "Default")
      (node (ref "U9") (pin "13") (pinfunction "CAS1_13") (pintype "output"))
    )
    (net (code "217") (name "unconnected-(U9-CAS2-Pad15)") (class "Default")
      (node (ref "U9") (pin "15") (pinfunction "CAS2_15") (pintype "output"))
    )
    (net (code "218") (name "unconnected-(U9-CS-Pad1)") (class "Default")
      (node (ref "U9") (pin "1") (pinfunction "CS_1") (pintype "input"))
    )
    (net (code "219") (name "unconnected-(U9-D2-Pad9)") (class "Default")
      (node (ref "U9") (pin "9") (pinfunction "D2_9") (pintype "bidirectional"))
    )
    (net (code "220") (name "unconnected-(U9-D3-Pad8)") (class "Default")
      (node (ref "U9") (pin "8") (pinfunction "D3_8") (pintype "bidirectional"))
    )
    (net (code "221") (name "unconnected-(U9-GND-Pad14)") (class "Default")
      (node (ref "U9") (pin "14") (pinfunction "GND_14") (pintype "bidirectional"))
    )
    (net (code "222") (name "unconnected-(U9-INT-Pad17)") (class "Default")
      (node (ref "U9") (pin "17") (pinfunction "INT_17") (pintype "output"))
    )
    (net (code "223") (name "unconnected-(U9-INTA-Pad26)") (class "Default")
      (node (ref "U9") (pin "26") (pinfunction "INTA_26") (pintype "input"))
    )
    (net (code "224") (name "unconnected-(U9-IR2-Pad20)") (class "Default")
      (node (ref "U9") (pin "20") (pinfunction "IR2_20") (pintype "input"))
    )
    (net (code "225") (name "unconnected-(U9-IR3-Pad21)") (class "Default")
      (node (ref "U9") (pin "21") (pinfunction "IR3_21") (pintype "input"))
    )
    (net (code "226") (name "unconnected-(U9-IR4-Pad22)") (class "Default")
      (node (ref "U9") (pin "22") (pinfunction "IR4_22") (pintype "input"))
    )
    (net (code "227") (name "unconnected-(U9-IR5-Pad23)") (class "Default")
      (node (ref "U9") (pin "23") (pinfunction "IR5_23") (pintype "input"))
    )
    (net (code "228") (name "unconnected-(U9-IR6-Pad24)") (class "Default")
      (node (ref "U9") (pin "24") (pinfunction "IR6_24") (pintype "input"))
    )
    (net (code "229") (name "unconnected-(U9-IR7-Pad25)") (class "Default")
      (node (ref "U9") (pin "25") (pinfunction "IR7_25") (pintype "input"))
    )
    (net (code "230") (name "unconnected-(U9-SP{slash}EN-Pad16)") (class "Default")
      (node (ref "U9") (pin "16") (pinfunction "SP/EN_16") (pintype "bidirectional"))
    )
    (net (code "231") (name "unconnected-(U9-VCC-Pad28)") (class "Default")
      (node (ref "U9") (pin "28") (pinfunction "VCC_28") (pintype "bidirectional"))
    )
    (net (code "232") (name "unconnected-(U10-A0-Pad19)") (class "Default")
      (node (ref "U10") (pin "19") (pinfunction "A0_19") (pintype "input"))
    )
    (net (code "233") (name "unconnected-(U10-A1-Pad20)") (class "Default")
      (node (ref "U10") (pin "20") (pinfunction "A1_20") (pintype "input"))
    )
    (net (code "234") (name "unconnected-(U10-CLK2-Pad18)") (class "Default")
      (node (ref "U10") (pin "18") (pinfunction "CLK2_18") (pintype "input"))
    )
    (net (code "235") (name "unconnected-(U10-CS-Pad21)") (class "Default")
      (node (ref "U10") (pin "21") (pinfunction "CS_21") (pintype "input"))
    )
    (net (code "236") (name "unconnected-(U10-G0-Pad11)") (class "Default")
      (node (ref "U10") (pin "11") (pinfunction "G0_11") (pintype "input"))
    )
    (net (code "237") (name "unconnected-(U10-G1-Pad14)") (class "Default")
      (node (ref "U10") (pin "14") (pinfunction "G1_14") (pintype "input"))
    )
    (net (code "238") (name "unconnected-(U10-G2-Pad16)") (class "Default")
      (node (ref "U10") (pin "16") (pinfunction "G2_16") (pintype "input"))
    )
    (net (code "239") (name "unconnected-(U10-GND-Pad12)") (class "Default")
      (node (ref "U10") (pin "12") (pinfunction "GND_12") (pintype "bidirectional"))
    )
    (net (code "240") (name "unconnected-(U10-OUT2-Pad17)") (class "Default")
      (node (ref "U10") (pin "17") (pinfunction "OUT2_17") (pintype "output"))
    )
    (net (code "241") (name "unconnected-(U10-VCC-Pad24)") (class "Default")
      (node (ref "U10") (pin "24") (pinfunction "VCC_24") (pintype "bidirectional"))
    )
    (net (code "242") (name "unconnected-(U11-!BHE!S7-Pad34)") (class "Default")
      (node (ref "U11") (pin "34") (pinfunction "!BHE!S7_34") (pintype "unspecified"))
    )
    (net (code "243") (name "unconnected-(U11-A16S3-Pad38)") (class "Default")
      (node (ref "U11") (pin "38") (pinfunction "A16S3_38") (pintype "unspecified"))
    )
    (net (code "244") (name "unconnected-(U11-A17S4-Pad37)") (class "Default")
      (node (ref "U11") (pin "37") (pinfunction "A17S4_37") (pintype "unspecified"))
    )
    (net (code "245") (name "unconnected-(U11-A18S5-Pad36)") (class "Default")
      (node (ref "U11") (pin "36") (pinfunction "A18S5_36") (pintype "unspecified"))
    )
    (net (code "246") (name "unconnected-(U11-A19S6-Pad35)") (class "Default")
      (node (ref "U11") (pin "35") (pinfunction "A19S6_35") (pintype "unspecified"))
    )
    (net (code "247") (name "unconnected-(U11-AD8-Pad8)") (class "Default")
      (node (ref "U11") (pin "8") (pinfunction "AD8_8") (pintype "unspecified"))
    )
    (net (code "248") (name "unconnected-(U11-AD9-Pad7)") (class "Default")
      (node (ref "U11") (pin "7") (pinfunction "AD9_7") (pintype "unspecified"))
    )
    (net (code "249") (name "unconnected-(U11-AD10-Pad6)") (class "Default")
      (node (ref "U11") (pin "6") (pinfunction "AD10_6") (pintype "unspecified"))
    )
    (net (code "250") (name "unconnected-(U11-AD11-Pad5)") (class "Default")
      (node (ref "U11") (pin "5") (pinfunction "AD11_5") (pintype "unspecified"))
    )
    (net (code "251") (name "unconnected-(U11-AD12-Pad4)") (class "Default")
      (node (ref "U11") (pin "4") (pinfunction "AD12_4") (pintype "unspecified"))
    )
    (net (code "252") (name "unconnected-(U11-AD13-Pad3)") (class "Default")
      (node (ref "U11") (pin "3") (pinfunction "AD13_3") (pintype "unspecified"))
    )
    (net (code "253") (name "unconnected-(U11-AD14-Pad2)") (class "Default")
      (node (ref "U11") (pin "2") (pinfunction "AD14_2") (pintype "unspecified"))
    )
    (net (code "254") (name "unconnected-(U11-AD15-Pad39)") (class "Default")
      (node (ref "U11") (pin "39") (pinfunction "AD15_39") (pintype "unspecified"))
    )
    (net (code "255") (name "unconnected-(U11-ALE-Pad25)") (class "Default")
      (node (ref "U11") (pin "25") (pinfunction "ALE_25") (pintype "unspecified"))
    )
    (net (code "256") (name "unconnected-(U11-DEN-Pad26)") (class "Default")
      (node (ref "U11") (pin "26") (pinfunction "DEN_26") (pintype "unspecified"))
    )
    (net (code "257") (name "unconnected-(U11-DT!R-Pad27)") (class "Default")
      (node (ref "U11") (pin "27") (pinfunction "DT!R_27") (pintype "unspecified"))
    )
    (net (code "258") (name "unconnected-(U11-GND-Pad1)") (class "Default")
      (node (ref "U11") (pin "1") (pinfunction "GND_1") (pintype "unspecified"))
    )
    (net (code "259") (name "unconnected-(U11-GND-Pad20)") (class "Default")
      (node (ref "U11") (pin "20") (pinfunction "GND_20") (pintype "unspecified"))
    )
    (net (code "260") (name "unconnected-(U11-HLDA-Pad30)") (class "Default")
      (node (ref "U11") (pin "30") (pinfunction "HLDA_30") (pintype "unspecified"))
    )
    (net (code "261") (name "unconnected-(U11-HOLD-Pad31)") (class "Default")
      (node (ref "U11") (pin "31") (pinfunction "HOLD_31") (pintype "unspecified"))
    )
    (net (code "262") (name "unconnected-(U11-INTA-Pad24)") (class "Default")
      (node (ref "U11") (pin "24") (pinfunction "INTA_24") (pintype "unspecified"))
    )
    (net (code "263") (name "unconnected-(U11-INTR-Pad18)") (class "Default")
      (node (ref "U11") (pin "18") (pinfunction "INTR_18") (pintype "unspecified"))
    )
    (net (code "264") (name "unconnected-(U11-M!IO-Pad28)") (class "Default")
      (node (ref "U11") (pin "28") (pinfunction "M!IO_28") (pintype "unspecified"))
    )
    (net (code "265") (name "unconnected-(U11-MN-Pad33)") (class "Default")
      (node (ref "U11") (pin "33") (pinfunction "MN_33") (pintype "unspecified"))
    )
    (net (code "266") (name "unconnected-(U11-NMI-Pad17)") (class "Default")
      (node (ref "U11") (pin "17") (pinfunction "NMI_17") (pintype "unspecified"))
    )
    (net (code "267") (name "unconnected-(U11-TEST-Pad23)") (class "Default")
      (node (ref "U11") (pin "23") (pinfunction "TEST_23") (pintype "unspecified"))
    )
    (net (code "268") (name "unconnected-(U11-VCC-Pad40)") (class "Default")
      (node (ref "U11") (pin "40") (pinfunction "VCC_40") (pintype "unspecified"))
    )
    (net (code "269") (name "unconnected-(U12-D0-Pad3)") (class "Default")
      (node (ref "U12") (pin "3") (pinfunction "D0_3") (pintype "unspecified"))
    )
    (net (code "270") (name "unconnected-(U12-D1-Pad4)") (class "Default")
      (node (ref "U12") (pin "4") (pinfunction "D1_4") (pintype "unspecified"))
    )
    (net (code "271") (name "unconnected-(U12-D2-Pad7)") (class "Default")
      (node (ref "U12") (pin "7") (pinfunction "D2_7") (pintype "unspecified"))
    )
    (net (code "272") (name "unconnected-(U12-D3-Pad8)") (class "Default")
      (node (ref "U12") (pin "8") (pinfunction "D3_8") (pintype "unspecified"))
    )
    (net (code "273") (name "unconnected-(U12-D4-Pad13)") (class "Default")
      (node (ref "U12") (pin "13") (pinfunction "D4_13") (pintype "unspecified"))
    )
    (net (code "274") (name "unconnected-(U12-D5-Pad14)") (class "Default")
      (node (ref "U12") (pin "14") (pinfunction "D5_14") (pintype "unspecified"))
    )
    (net (code "275") (name "unconnected-(U12-D6-Pad17)") (class "Default")
      (node (ref "U12") (pin "17") (pinfunction "D6_17") (pintype "unspecified"))
    )
    (net (code "276") (name "unconnected-(U12-D7-Pad18)") (class "Default")
      (node (ref "U12") (pin "18") (pinfunction "D7_18") (pintype "unspecified"))
    )
    (net (code "277") (name "unconnected-(U12-GND-Pad10)") (class "Default")
      (node (ref "U12") (pin "10") (pinfunction "GND_10") (pintype "unspecified"))
    )
    (net (code "278") (name "unconnected-(U12-Q0-Pad2)") (class "Default")
      (node (ref "U12") (pin "2") (pinfunction "Q0_2") (pintype "unspecified"))
    )
    (net (code "279") (name "unconnected-(U12-Q1-Pad5)") (class "Default")
      (node (ref "U12") (pin "5") (pinfunction "Q1_5") (pintype "unspecified"))
    )
    (net (code "280") (name "unconnected-(U12-Q2-Pad6)") (class "Default")
      (node (ref "U12") (pin "6") (pinfunction "Q2_6") (pintype "unspecified"))
    )
    (net (code "281") (name "unconnected-(U12-Q3-Pad9)") (class "Default")
      (node (ref "U12") (pin "9") (pinfunction "Q3_9") (pintype "unspecified"))
    )
    (net (code "282") (name "unconnected-(U12-Q4-Pad12)") (class "Default")
      (node (ref "U12") (pin "12") (pinfunction "Q4_12") (pintype "unspecified"))
    )
    (net (code "283") (name "unconnected-(U12-Q5-Pad15)") (class "Default")
      (node (ref "U12") (pin "15") (pinfunction "Q5_15") (pintype "unspecified"))
    )
    (net (code "284") (name "unconnected-(U12-Q6-Pad16)") (class "Default")
      (node (ref "U12") (pin "16") (pinfunction "Q6_16") (pintype "unspecified"))
    )
    (net (code "285") (name "unconnected-(U12-Q7-Pad19)") (class "Default")
      (node (ref "U12") (pin "19") (pinfunction "Q7_19") (pintype "unspecified"))
    )
    (net (code "286") (name "unconnected-(U12-VCC-Pad20)") (class "Default")
      (node (ref "U12") (pin "20") (pinfunction "VCC_20") (pintype "unspecified"))
    )
    (net (code "287") (name "unconnected-(U13-D6-Pad17)") (class "Default")
      (node (ref "U13") (pin "17") (pinfunction "D6_17") (pintype "unspecified"))
    )
    (net (code "288") (name "unconnected-(U13-D7-Pad18)") (class "Default")
      (node (ref "U13") (pin "18") (pinfunction "D7_18") (pintype "unspecified"))
    )
    (net (code "289") (name "unconnected-(U13-GND-Pad10)") (class "Default")
      (node (ref "U13") (pin "10") (pinfunction "GND_10") (pintype "unspecified"))
    )
    (net (code "290") (name "unconnected-(U13-Q0-Pad2)") (class "Default")
      (node (ref "U13") (pin "2") (pinfunction "Q0_2") (pintype "unspecified"))
    )
    (net (code "291") (name "unconnected-(U13-Q1-Pad5)") (class "Default")
      (node (ref "U13") (pin "5") (pinfunction "Q1_5") (pintype "unspecified"))
    )
    (net (code "292") (name "unconnected-(U13-Q2-Pad6)") (class "Default")
      (node (ref "U13") (pin "6") (pinfunction "Q2_6") (pintype "unspecified"))
    )
    (net (code "293") (name "unconnected-(U13-Q3-Pad9)") (class "Default")
      (node (ref "U13") (pin "9") (pinfunction "Q3_9") (pintype "unspecified"))
    )
    (net (code "294") (name "unconnected-(U13-Q4-Pad12)") (class "Default")
      (node (ref "U13") (pin "12") (pinfunction "Q4_12") (pintype "unspecified"))
    )
    (net (code "295") (name "unconnected-(U13-Q5-Pad15)") (class "Default")
      (node (ref "U13") (pin "15") (pinfunction "Q5_15") (pintype "unspecified"))
    )
    (net (code "296") (name "unconnected-(U13-Q6-Pad16)") (class "Default")
      (node (ref "U13") (pin "16") (pinfunction "Q6_16") (pintype "unspecified"))
    )
    (net (code "297") (name "unconnected-(U13-Q7-Pad19)") (class "Default")
      (node (ref "U13") (pin "19") (pinfunction "Q7_19") (pintype "unspecified"))
    )
    (net (code "298") (name "unconnected-(U13-VCC-Pad20)") (class "Default")
      (node (ref "U13") (pin "20") (pinfunction "VCC_20") (pintype "unspecified"))
    )
    (net (code "299") (name "unconnected-(U14-GCLK1-Pad37)") (class "Default")
      (node (ref "U14") (pin "37") (pinfunction "GCLK1_37") (pintype "unspecified"))
    )
    (net (code "300") (name "unconnected-(U14-GCLK2-Pad40)") (class "Default")
      (node (ref "U14") (pin "40") (pinfunction "GCLK2_40") (pintype "unspecified"))
    )
    (net (code "301") (name "unconnected-(U14-GCLRn-Pad39)") (class "Default")
      (node (ref "U14") (pin "39") (pinfunction "GCLRn_39") (pintype "unspecified"))
    )
    (net (code "302") (name "unconnected-(U14-GND-Pad4)") (class "Default")
      (node (ref "U14") (pin "4") (pinfunction "GND_4") (pintype "unspecified"))
    )
    (net (code "303") (name "unconnected-(U14-GND-Pad11)") (class "Default")
      (node (ref "U14") (pin "11") (pinfunction "GND_11") (pintype "unspecified"))
    )
    (net (code "304") (name "unconnected-(U14-GND-Pad16)") (class "Default")
      (node (ref "U14") (pin "16") (pinfunction "GND_16") (pintype "unspecified"))
    )
    (net (code "305") (name "unconnected-(U14-GND-Pad24)") (class "Default")
      (node (ref "U14") (pin "24") (pinfunction "GND_24") (pintype "unspecified"))
    )
    (net (code "306") (name "unconnected-(U14-GND-Pad30)") (class "Default")
      (node (ref "U14") (pin "30") (pinfunction "GND_30") (pintype "unspecified"))
    )
    (net (code "307") (name "unconnected-(U14-GND-Pad36)") (class "Default")
      (node (ref "U14") (pin "36") (pinfunction "GND_36") (pintype "unspecified"))
    )
    (net (code "308") (name "unconnected-(U14-OE1-Pad38)") (class "Default")
      (node (ref "U14") (pin "38") (pinfunction "OE1_38") (pintype "unspecified"))
    )
    (net (code "309") (name "unconnected-(U14-PA1-Pad42)") (class "Default")
      (node (ref "U14") (pin "42") (pinfunction "PA1_42") (pintype "unspecified"))
    )
    (net (code "310") (name "unconnected-(U14-PA2-Pad43)") (class "Default")
      (node (ref "U14") (pin "43") (pinfunction "PA2_43") (pintype "unspecified"))
    )
    (net (code "311") (name "unconnected-(U14-PA3-Pad44)") (class "Default")
      (node (ref "U14") (pin "44") (pinfunction "PA3_44") (pintype "unspecified"))
    )
    (net (code "312") (name "unconnected-(U14-PA5-Pad2)") (class "Default")
      (node (ref "U14") (pin "2") (pinfunction "PA5_2") (pintype "unspecified"))
    )
    (net (code "313") (name "unconnected-(U14-PA6-Pad3)") (class "Default")
      (node (ref "U14") (pin "3") (pinfunction "PA6_3") (pintype "unspecified"))
    )
    (net (code "314") (name "unconnected-(U14-PA7-Pad5)") (class "Default")
      (node (ref "U14") (pin "5") (pinfunction "PA7_5") (pintype "unspecified"))
    )
    (net (code "315") (name "unconnected-(U14-PA8-Pad6)") (class "Default")
      (node (ref "U14") (pin "6") (pinfunction "PA8_6") (pintype "unspecified"))
    )
    (net (code "316") (name "unconnected-(U14-PA10-Pad8)") (class "Default")
      (node (ref "U14") (pin "8") (pinfunction "PA10_8") (pintype "unspecified"))
    )
    (net (code "317") (name "unconnected-(U14-PA11-Pad10)") (class "Default")
      (node (ref "U14") (pin "10") (pinfunction "PA11_10") (pintype "unspecified"))
    )
    (net (code "318") (name "unconnected-(U14-PA13-Pad12)") (class "Default")
      (node (ref "U14") (pin "12") (pinfunction "PA13_12") (pintype "unspecified"))
    )
    (net (code "319") (name "unconnected-(U14-PA14-Pad13)") (class "Default")
      (node (ref "U14") (pin "13") (pinfunction "PA14_13") (pintype "unspecified"))
    )
    (net (code "320") (name "unconnected-(U14-PA15-Pad14)") (class "Default")
      (node (ref "U14") (pin "14") (pinfunction "PA15_14") (pintype "unspecified"))
    )
    (net (code "321") (name "unconnected-(U14-PA16-Pad15)") (class "Default")
      (node (ref "U14") (pin "15") (pinfunction "PA16_15") (pintype "unspecified"))
    )
    (net (code "322") (name "unconnected-(U14-PB17-Pad35)") (class "Default")
      (node (ref "U14") (pin "35") (pinfunction "PB17_35") (pintype "unspecified"))
    )
    (net (code "323") (name "unconnected-(U14-PB18-Pad34)") (class "Default")
      (node (ref "U14") (pin "34") (pinfunction "PB18_34") (pintype "unspecified"))
    )
    (net (code "324") (name "unconnected-(U14-PB19-Pad33)") (class "Default")
      (node (ref "U14") (pin "33") (pinfunction "PB19_33") (pintype "unspecified"))
    )
    (net (code "325") (name "unconnected-(U14-PB21-Pad31)") (class "Default")
      (node (ref "U14") (pin "31") (pinfunction "PB21_31") (pintype "unspecified"))
    )
    (net (code "326") (name "unconnected-(U14-PB23-Pad28)") (class "Default")
      (node (ref "U14") (pin "28") (pinfunction "PB23_28") (pintype "unspecified"))
    )
    (net (code "327") (name "unconnected-(U14-PB24-Pad27)") (class "Default")
      (node (ref "U14") (pin "27") (pinfunction "PB24_27") (pintype "unspecified"))
    )
    (net (code "328") (name "unconnected-(U14-PB26-Pad25)") (class "Default")
      (node (ref "U14") (pin "25") (pinfunction "PB26_25") (pintype "unspecified"))
    )
    (net (code "329") (name "unconnected-(U14-PB27-Pad23)") (class "Default")
      (node (ref "U14") (pin "23") (pinfunction "PB27_23") (pintype "unspecified"))
    )
    (net (code "330") (name "unconnected-(U14-PB28-Pad22)") (class "Default")
      (node (ref "U14") (pin "22") (pinfunction "PB28_22") (pintype "unspecified"))
    )
    (net (code "331") (name "unconnected-(U14-PB29-Pad21)") (class "Default")
      (node (ref "U14") (pin "21") (pinfunction "PB29_21") (pintype "unspecified"))
    )
    (net (code "332") (name "unconnected-(U14-PB30-Pad20)") (class "Default")
      (node (ref "U14") (pin "20") (pinfunction "PB30_20") (pintype "unspecified"))
    )
    (net (code "333") (name "unconnected-(U14-PB31-Pad19)") (class "Default")
      (node (ref "U14") (pin "19") (pinfunction "PB31_19") (pintype "unspecified"))
    )
    (net (code "334") (name "unconnected-(U14-PB32-Pad18)") (class "Default")
      (node (ref "U14") (pin "18") (pinfunction "PB32_18") (pintype "unspecified"))
    )
    (net (code "335") (name "unconnected-(U14-TCK-Pad26)") (class "Default")
      (node (ref "U14") (pin "26") (pinfunction "TCK_26") (pintype "unspecified"))
    )
    (net (code "336") (name "unconnected-(U14-TDI-Pad1)") (class "Default")
      (node (ref "U14") (pin "1") (pinfunction "TDI_1") (pintype "unspecified"))
    )
    (net (code "337") (name "unconnected-(U14-TDO-Pad32)") (class "Default")
      (node (ref "U14") (pin "32") (pinfunction "TDO_32") (pintype "unspecified"))
    )
    (net (code "338") (name "unconnected-(U14-TMS-Pad7)") (class "Default")
      (node (ref "U14") (pin "7") (pinfunction "TMS_7") (pintype "unspecified"))
    )
    (net (code "339") (name "unconnected-(U14-VCC-Pad9)") (class "Default")
      (node (ref "U14") (pin "9") (pinfunction "VCC_9") (pintype "unspecified"))
    )
    (net (code "340") (name "unconnected-(U14-VCC-Pad17)") (class "Default")
      (node (ref "U14") (pin "17") (pinfunction "VCC_17") (pintype "unspecified"))
    )
    (net (code "341") (name "unconnected-(U14-VCC-Pad29)") (class "Default")
      (node (ref "U14") (pin "29") (pinfunction "VCC_29") (pintype "unspecified"))
    )
    (net (code "342") (name "unconnected-(U14-VCC-Pad41)") (class "Default")
      (node (ref "U14") (pin "41") (pinfunction "VCC_41") (pintype "unspecified"))
    )
    (net (code "343") (name "unconnected-(U18-Padcom)") (class "Default")
      (node (ref "U18") (pin "com") (pinfunction "com_com") (pintype "passive"))
    )
    (net (code "344") (name "unconnected-(U19-A0-Pad9)") (class "Default")
      (node (ref "U19") (pin "9") (pinfunction "A0_9") (pintype "input"))
    )
    (net (code "345") (name "unconnected-(U19-A1-Pad8)") (class "Default")
      (node (ref "U19") (pin "8") (pinfunction "A1_8") (pintype "input"))
    )
    (net (code "346") (name "unconnected-(U19-CS-Pad6)") (class "Default")
      (node (ref "U19") (pin "6") (pinfunction "CS_6") (pintype "input"))
    )
    (net (code "347") (name "unconnected-(U19-D4-Pad30)") (class "Default")
      (node (ref "U19") (pin "30") (pinfunction "D4_30") (pintype "bidirectional"))
    )
    (net (code "348") (name "unconnected-(U19-GND-Pad7)") (class "Default")
      (node (ref "U19") (pin "7") (pinfunction "GND_7") (pintype "bidirectional"))
    )
    (net (code "349") (name "unconnected-(U19-PA0-Pad4)") (class "Default")
      (node (ref "U19") (pin "4") (pinfunction "PA0_4") (pintype "bidirectional"))
    )
    (net (code "350") (name "unconnected-(U19-PA1-Pad3)") (class "Default")
      (node (ref "U19") (pin "3") (pinfunction "PA1_3") (pintype "bidirectional"))
    )
    (net (code "351") (name "unconnected-(U19-PA2-Pad2)") (class "Default")
      (node (ref "U19") (pin "2") (pinfunction "PA2_2") (pintype "bidirectional"))
    )
    (net (code "352") (name "unconnected-(U19-PA3-Pad1)") (class "Default")
      (node (ref "U19") (pin "1") (pinfunction "PA3_1") (pintype "bidirectional"))
    )
    (net (code "353") (name "unconnected-(U19-PA4-Pad40)") (class "Default")
      (node (ref "U19") (pin "40") (pinfunction "PA4_40") (pintype "bidirectional"))
    )
    (net (code "354") (name "unconnected-(U19-PA5-Pad39)") (class "Default")
      (node (ref "U19") (pin "39") (pinfunction "PA5_39") (pintype "bidirectional"))
    )
    (net (code "355") (name "unconnected-(U19-PA6-Pad38)") (class "Default")
      (node (ref "U19") (pin "38") (pinfunction "PA6_38") (pintype "bidirectional"))
    )
    (net (code "356") (name "unconnected-(U19-PA7-Pad37)") (class "Default")
      (node (ref "U19") (pin "37") (pinfunction "PA7_37") (pintype "bidirectional"))
    )
    (net (code "357") (name "unconnected-(U19-PB4-Pad22)") (class "Default")
      (node (ref "U19") (pin "22") (pinfunction "PB4_22") (pintype "bidirectional"))
    )
    (net (code "358") (name "unconnected-(U19-PB5-Pad23)") (class "Default")
      (node (ref "U19") (pin "23") (pinfunction "PB5_23") (pintype "bidirectional"))
    )
    (net (code "359") (name "unconnected-(U19-PB6-Pad24)") (class "Default")
      (node (ref "U19") (pin "24") (pinfunction "PB6_24") (pintype "bidirectional"))
    )
    (net (code "360") (name "unconnected-(U19-PB7-Pad25)") (class "Default")
      (node (ref "U19") (pin "25") (pinfunction "PB7_25") (pintype "bidirectional"))
    )
    (net (code "361") (name "unconnected-(U19-PC0-Pad14)") (class "Default")
      (node (ref "U19") (pin "14") (pinfunction "PC0_14") (pintype "bidirectional"))
    )
    (net (code "362") (name "unconnected-(U19-PC1-Pad15)") (class "Default")
      (node (ref "U19") (pin "15") (pinfunction "PC1_15") (pintype "bidirectional"))
    )
    (net (code "363") (name "unconnected-(U19-PC2-Pad16)") (class "Default")
      (node (ref "U19") (pin "16") (pinfunction "PC2_16") (pintype "bidirectional"))
    )
    (net (code "364") (name "unconnected-(U19-PC3-Pad17)") (class "Default")
      (node (ref "U19") (pin "17") (pinfunction "PC3_17") (pintype "bidirectional"))
    )
    (net (code "365") (name "unconnected-(U19-PC4-Pad13)") (class "Default")
      (node (ref "U19") (pin "13") (pinfunction "PC4_13") (pintype "bidirectional"))
    )
    (net (code "366") (name "unconnected-(U19-PC5-Pad12)") (class "Default")
      (node (ref "U19") (pin "12") (pinfunction "PC5_12") (pintype "bidirectional"))
    )
    (net (code "367") (name "unconnected-(U19-PC6-Pad11)") (class "Default")
      (node (ref "U19") (pin "11") (pinfunction "PC6_11") (pintype "bidirectional"))
    )
    (net (code "368") (name "unconnected-(U19-PC7-Pad10)") (class "Default")
      (node (ref "U19") (pin "10") (pinfunction "PC7_10") (pintype "bidirectional"))
    )
    (net (code "369") (name "unconnected-(U19-RESET-Pad35)") (class "Default")
      (node (ref "U19") (pin "35") (pinfunction "RESET_35") (pintype "input"))
    )
    (net (code "370") (name "unconnected-(U19-VCC-Pad26)") (class "Default")
      (node (ref "U19") (pin "26") (pinfunction "VCC_26") (pintype "bidirectional"))
    )
    (net (code "371") (name "unconnected-(U19-WR-Pad36)") (class "Default")
      (node (ref "U19") (pin "36") (pinfunction "WR_36") (pintype "input"))
    )
  )
)
